# minimal.net
KiCad netlist of a schematic drawn in EAGLE
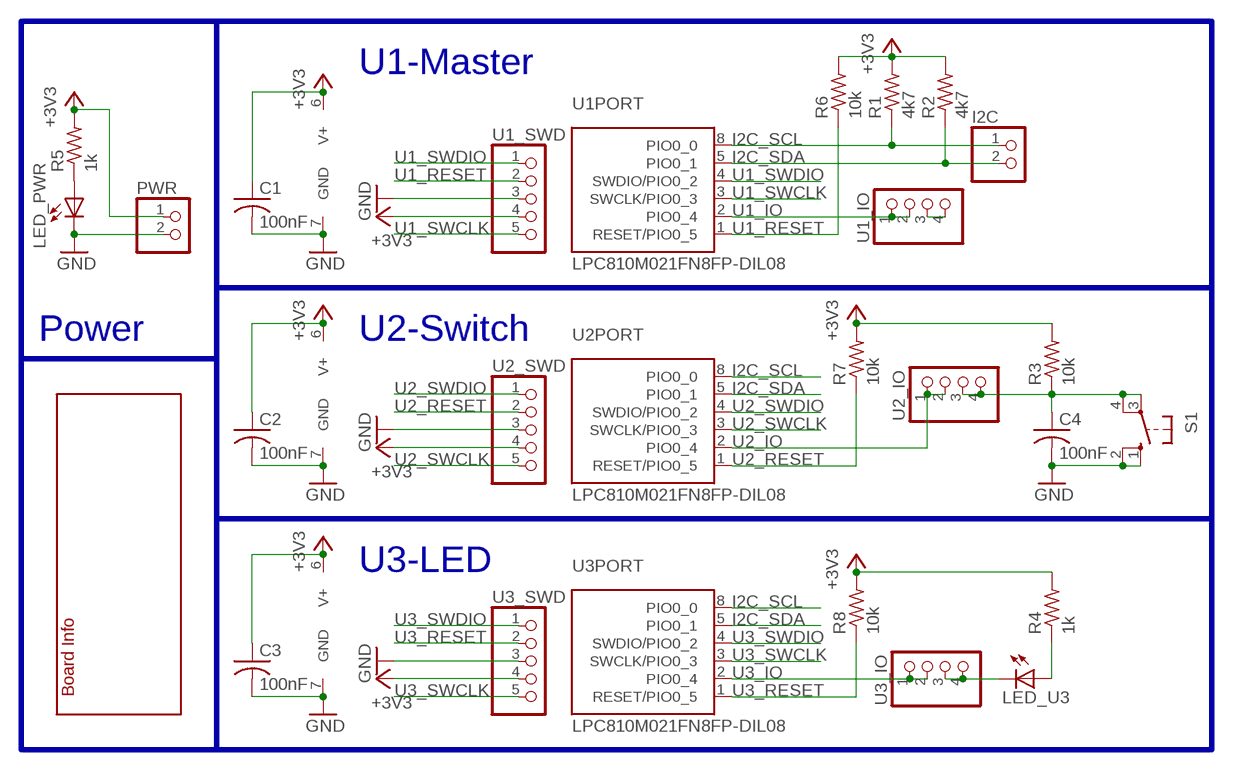
[diagram p0: schematic, sheet 1]

(export (version "E")
  (design (tool "Eeschema 10.0.6"))
  (components
    (comp (ref "C1")
      (value "100nF")
      (footprint "eagle-import:C025-025X050")
      (libsource (lib "eagle-import") (part "C-US025-025X050"))
    )
    (comp (ref "C2")
      (value "100nF")
      (footprint "eagle-import:C025-025X050")
      (libsource (lib "eagle-import") (part "C-US025-025X050"))
    )
    (comp (ref "C3")
      (value "100nF")
      (footprint "eagle-import:C025-025X050")
      (libsource (lib "eagle-import") (part "C-US025-025X050"))
    )
    (comp (ref "C4")
      (value "100nF")
      (footprint "eagle-import:C025-025X050")
      (libsource (lib "eagle-import") (part "C-US025-025X050"))
    )
    (comp (ref "I2C")
      (value "PINHD-1X2")
      (footprint "eagle-import:1X02")
      (libsource (lib "eagle-import") (part "PINHD-1X2"))
    )
    (comp (ref "LED_PWR")
      (value "LED5MM")
      (footprint "eagle-import:LED5MM")
      (libsource (lib "eagle-import") (part "LED5MM"))
    )
    (comp (ref "LED_U3")
      (value "LED5MM")
      (footprint "eagle-import:LED5MM")
      (libsource (lib "eagle-import") (part "LED5MM"))
    )
    (comp (ref "PWR")
      (value "PINHD-1X2")
      (footprint "eagle-import:1X02")
      (libsource (lib "eagle-import") (part "PINHD-1X2"))
    )
    (comp (ref "R1")
      (value "4k7")
      (footprint "eagle-import:0204V")
      (libsource (lib "eagle-import") (part "R-US_0204/2V"))
    )
    (comp (ref "R2")
      (value "4k7")
      (footprint "eagle-import:0204V")
      (libsource (lib "eagle-import") (part "R-US_0204/2V"))
    )
    (comp (ref "R3")
      (value "10k")
      (footprint "eagle-import:0204V")
      (libsource (lib "eagle-import") (part "R-US_0204/2V"))
    )
    (comp (ref "R4")
      (value "1k")
      (footprint "eagle-import:0204V")
      (libsource (lib "eagle-import") (part "R-US_0204/2V"))
    )
    (comp (ref "R5")
      (value "1k")
      (footprint "eagle-import:0204V")
      (libsource (lib "eagle-import") (part "R-US_0204/2V"))
    )
    (comp (ref "R6")
      (value "10k")
      (footprint "eagle-import:0204V")
      (libsource (lib "eagle-import") (part "R-US_0204/2V"))
    )
    (comp (ref "R7")
      (value "10k")
      (footprint "eagle-import:0204V")
      (libsource (lib "eagle-import") (part "R-US_0204/2V"))
    )
    (comp (ref "R8")
      (value "10k")
      (footprint "eagle-import:0204V")
      (libsource (lib "eagle-import") (part "R-US_0204/2V"))
    )
    (comp (ref "S1")
      (value "10-XX")
      (footprint "eagle-import:B3F-10XX")
      (fields (field (name "MPN") "B3F-1000"))
      (libsource (lib "eagle-import") (part "10-XX"))
    )
    (comp (ref "U$1")
      (value "INFO")
      (footprint "eagle-import:INFO")
      (fields
        (field (name "AUTHOR") "Austin Buchan")
        (field (name "DATE") "May 29, 2015")
        (field (name "DESIGN") "MinimalModRob")
        (field (name "ORGANIZATION") "UC Berkeley ASPIRE")
        (field (name "REVISION") "r0.0")
      )
      (libsource (lib "eagle-import") (part "INFO"))
    )
    (comp (ref "U1")
      (value "LPC810M021FN8FP-DIL08")
      (footprint "eagle-import:DIL08")
      (libsource (lib "eagle-import") (part "LPC810M021FN8FP-DIL08"))
    )
    (comp (ref "U1_IO")
      (value "PINHD-1X4")
      (footprint "eagle-import:1X04")
      (libsource (lib "eagle-import") (part "PINHD-1X4"))
    )
    (comp (ref "U1_SWD")
      (value "PINHD-1X5")
      (footprint "eagle-import:1X05")
      (libsource (lib "eagle-import") (part "PINHD-1X5"))
    )
    (comp (ref "U2")
      (value "LPC810M021FN8FP-DIL08")
      (footprint "eagle-import:DIL08")
      (libsource (lib "eagle-import") (part "LPC810M021FN8FP-DIL08"))
    )
    (comp (ref "U2_IO")
      (value "PINHD-1X4")
      (footprint "eagle-import:1X04")
      (libsource (lib "eagle-import") (part "PINHD-1X4"))
    )
    (comp (ref "U2_SWD")
      (value "PINHD-1X5")
      (footprint "eagle-import:1X05")
      (libsource (lib "eagle-import") (part "PINHD-1X5"))
    )
    (comp (ref "U3")
      (value "LPC810M021FN8FP-DIL08")
      (footprint "eagle-import:DIL08")
      (libsource (lib "eagle-import") (part "LPC810M021FN8FP-DIL08"))
    )
    (comp (ref "U3_IO")
      (value "PINHD-1X4")
      (footprint "eagle-import:1X04")
      (libsource (lib "eagle-import") (part "PINHD-1X4"))
    )
    (comp (ref "U3_SWD")
      (value "PINHD-1X5")
      (footprint "eagle-import:1X05")
      (libsource (lib "eagle-import") (part "PINHD-1X5"))
    )
  )
  (nets
    (net (code "1") (name "+3V3") (class "Default")
      (node (ref "C1") (pin "1") (pinfunction "1_1") (pintype "passive"))
      (node (ref "C2") (pin "1") (pinfunction "1_1") (pintype "passive"))
      (node (ref "C3") (pin "1") (pinfunction "1_1") (pintype "passive"))
      (node (ref "PWR") (pin "1") (pinfunction "1_1") (pintype "passive"))
      (node (ref "R1") (pin "2") (pinfunction "2_2") (pintype "passive"))
      (node (ref "R2") (pin "2") (pinfunction "2_2") (pintype "passive"))
      (node (ref "R3") (pin "2") (pinfunction "2_2") (pintype "passive"))
      (node (ref "R4") (pin "2") (pinfunction "2_2") (pintype "passive"))
      (node (ref "R5") (pin "2") (pinfunction "2_2") (pintype "passive"))
      (node (ref "R6") (pin "2") (pinfunction "2_2") (pintype "passive"))
      (node (ref "R7") (pin "2") (pinfunction "2_2") (pintype "passive"))
      (node (ref "R8") (pin "2") (pinfunction "2_2") (pintype "passive"))
      (node (ref "U1") (pin "6") (pinfunction "V+_6") (pintype "power_in"))
      (node (ref "U1_SWD") (pin "4") (pinfunction "4_4") (pintype "passive"))
      (node (ref "U2") (pin "6") (pinfunction "V+_6") (pintype "power_in"))
      (node (ref "U2_SWD") (pin "4") (pinfunction "4_4") (pintype "passive"))
      (node (ref "U3") (pin "6") (pinfunction "V+_6") (pintype "power_in"))
      (node (ref "U3_SWD") (pin "4") (pinfunction "4_4") (pintype "passive"))
    )
    (net (code "2") (name "/I2C_SCL") (class "Default")
      (node (ref "I2C") (pin "1") (pinfunction "1_1") (pintype "passive"))
      (node (ref "R1") (pin "1") (pinfunction "1_1") (pintype "passive"))
      (node (ref "U1") (pin "8") (pinfunction "PIO0_0_8") (pintype "bidirectional"))
      (node (ref "U2") (pin "8") (pinfunction "PIO0_0_8") (pintype "bidirectional"))
      (node (ref "U3") (pin "8") (pinfunction "PIO0_0_8") (pintype "bidirectional"))
    )
    (net (code "3") (name "/I2C_SDA") (class "Default")
      (node (ref "I2C") (pin "2") (pinfunction "2_2") (pintype "passive"))
      (node (ref "R2") (pin "1") (pinfunction "1_1") (pintype "passive"))
      (node (ref "U1") (pin "5") (pinfunction "PIO0_1_5") (pintype "bidirectional"))
      (node (ref "U2") (pin "5") (pinfunction "PIO0_1_5") (pintype "bidirectional"))
      (node (ref "U3") (pin "5") (pinfunction "PIO0_1_5") (pintype "bidirectional"))
    )
    (net (code "4") (name "/U1_IO") (class "Default")
      (node (ref "U1") (pin "2") (pinfunction "PIO0_4_2") (pintype "bidirectional"))
      (node (ref "U1_IO") (pin "1") (pinfunction "1_1") (pintype "passive"))
      (node (ref "U1_IO") (pin "2") (pinfunction "2_2") (pintype "passive"))
    )
    (net (code "5") (name "/U1_RESET") (class "Default")
      (node (ref "R6") (pin "1") (pinfunction "1_1") (pintype "passive"))
      (node (ref "U1") (pin "1") (pinfunction "RESET/PIO0_5_1") (pintype "bidirectional"))
      (node (ref "U1_SWD") (pin "2") (pinfunction "2_2") (pintype "passive"))
    )
    (net (code "6") (name "/U1_SWCLK") (class "Default")
      (node (ref "U1") (pin "3") (pinfunction "SWCLK/PIO0_3_3") (pintype "bidirectional"))
      (node (ref "U1_SWD") (pin "5") (pinfunction "5_5") (pintype "passive"))
    )
    (net (code "7") (name "/U1_SWDIO") (class "Default")
      (node (ref "U1") (pin "4") (pinfunction "SWDIO/PIO0_2_4") (pintype "bidirectional"))
      (node (ref "U1_SWD") (pin "1") (pinfunction "1_1") (pintype "passive"))
    )
    (net (code "8") (name "/U2_IO") (class "Default")
      (node (ref "U2") (pin "2") (pinfunction "PIO0_4_2") (pintype "bidirectional"))
      (node (ref "U2_IO") (pin "1") (pinfunction "1_1") (pintype "passive"))
      (node (ref "U2_IO") (pin "2") (pinfunction "2_2") (pintype "passive"))
    )
    (net (code "9") (name "/U2_RESET") (class "Default")
      (node (ref "R7") (pin "1") (pinfunction "1_1") (pintype "passive"))
      (node (ref "U2") (pin "1") (pinfunction "RESET/PIO0_5_1") (pintype "bidirectional"))
      (node (ref "U2_SWD") (pin "2") (pinfunction "2_2") (pintype "passive"))
    )
    (net (code "10") (name "/U2_SWCLK") (class "Default")
      (node (ref "U2") (pin "3") (pinfunction "SWCLK/PIO0_3_3") (pintype "bidirectional"))
      (node (ref "U2_SWD") (pin "5") (pinfunction "5_5") (pintype "passive"))
    )
    (net (code "11") (name "/U2_SWDIO") (class "Default")
      (node (ref "U2") (pin "4") (pinfunction "SWDIO/PIO0_2_4") (pintype "bidirectional"))
      (node (ref "U2_SWD") (pin "1") (pinfunction "1_1") (pintype "passive"))
    )
    (net (code "12") (name "/U3_IO") (class "Default")
      (node (ref "U3") (pin "2") (pinfunction "PIO0_4_2") (pintype "bidirectional"))
      (node (ref "U3_IO") (pin "1") (pinfunction "1_1") (pintype "passive"))
      (node (ref "U3_IO") (pin "2") (pinfunction "2_2") (pintype "passive"))
    )
    (net (code "13") (name "/U3_RESET") (class "Default")
      (node (ref "R8") (pin "1") (pinfunction "1_1") (pintype "passive"))
      (node (ref "U3") (pin "1") (pinfunction "RESET/PIO0_5_1") (pintype "bidirectional"))
      (node (ref "U3_SWD") (pin "2") (pinfunction "2_2") (pintype "passive"))
    )
    (net (code "14") (name "/U3_SWCLK") (class "Default")
      (node (ref "U3") (pin "3") (pinfunction "SWCLK/PIO0_3_3") (pintype "bidirectional"))
      (node (ref "U3_SWD") (pin "5") (pinfunction "5_5") (pintype "passive"))
    )
    (net (code "15") (name "/U3_SWDIO") (class "Default")
      (node (ref "U3") (pin "4") (pinfunction "SWDIO/PIO0_2_4") (pintype "bidirectional"))
      (node (ref "U3_SWD") (pin "1") (pinfunction "1_1") (pintype "passive"))
    )
    (net (code "16") (name "GND") (class "Default")
      (node (ref "C1") (pin "2") (pinfunction "2_2") (pintype "passive"))
      (node (ref "C2") (pin "2") (pinfunction "2_2") (pintype "passive"))
      (node (ref "C3") (pin "2") (pinfunction "2_2") (pintype "passive"))
      (node (ref "C4") (pin "2") (pinfunction "2_2") (pintype "passive"))
      (node (ref "LED_PWR") (pin "K") (pinfunction "C_K") (pintype "passive"))
      (node (ref "PWR") (pin "2") (pinfunction "2_2") (pintype "passive"))
      (node (ref "S1") (pin "1") (pinfunction "S_1") (pintype "passive"))
      (node (ref "S1") (pin "2") (pinfunction "S1_2") (pintype "passive"))
      (node (ref "U1") (pin "7") (pinfunction "GND_7") (pintype "power_in"))
      (node (ref "U1_SWD") (pin "3") (pinfunction "3_3") (pintype "passive"))
      (node (ref "U2") (pin "7") (pinfunction "GND_7") (pintype "power_in"))
      (node (ref "U2_SWD") (pin "3") (pinfunction "3_3") (pintype "passive"))
      (node (ref "U3") (pin "7") (pinfunction "GND_7") (pintype "power_in"))
      (node (ref "U3_SWD") (pin "3") (pinfunction "3_3") (pintype "passive"))
    )
    (net (code "17") (name "Net-(LED_PWR-PadA)") (class "Default")
      (node (ref "LED_PWR") (pin "A") (pinfunction "A_A") (pintype "passive"))
      (node (ref "R5") (pin "1") (pinfunction "1_1") (pintype "passive"))
    )
    (net (code "18") (name "Net-(LED_U3-C)") (class "Default")
      (node (ref "LED_U3") (pin "K") (pinfunction "C_K") (pintype "passive"))
      (node (ref "U3_IO") (pin "3") (pinfunction "3_3") (pintype "passive"))
      (node (ref "U3_IO") (pin "4") (pinfunction "4_4") (pintype "passive"))
    )
    (net (code "19") (name "Net-(LED_U3-PadA)") (class "Default")
      (node (ref "LED_U3") (pin "A") (pinfunction "A_A") (pintype "passive"))
      (node (ref "R4") (pin "1") (pinfunction "1_1") (pintype "passive"))
    )
    (net (code "20") (name "Net-(S1-P)") (class "Default")
      (node (ref "C4") (pin "1") (pinfunction "1_1") (pintype "passive"))
      (node (ref "R3") (pin "1") (pinfunction "1_1") (pintype "passive"))
      (node (ref "S1") (pin "3") (pinfunction "P_3") (pintype "passive"))
      (node (ref "S1") (pin "4") (pinfunction "P1_4") (pintype "passive"))
      (node (ref "U2_IO") (pin "3") (pinfunction "3_3") (pintype "passive"))
      (node (ref "U2_IO") (pin "4") (pinfunction "4_4") (pintype "passive"))
    )
    (net (code "21") (name "Net-(U1_IO-Pad3)") (class "Default")
      (node (ref "U1_IO") (pin "3") (pinfunction "3_3") (pintype "passive"))
      (node (ref "U1_IO") (pin "4") (pinfunction "4_4") (pintype "passive"))
    )
  )
)
